# LED_ring.net
KiCad netlist of a schematic drawn in Altium Designer
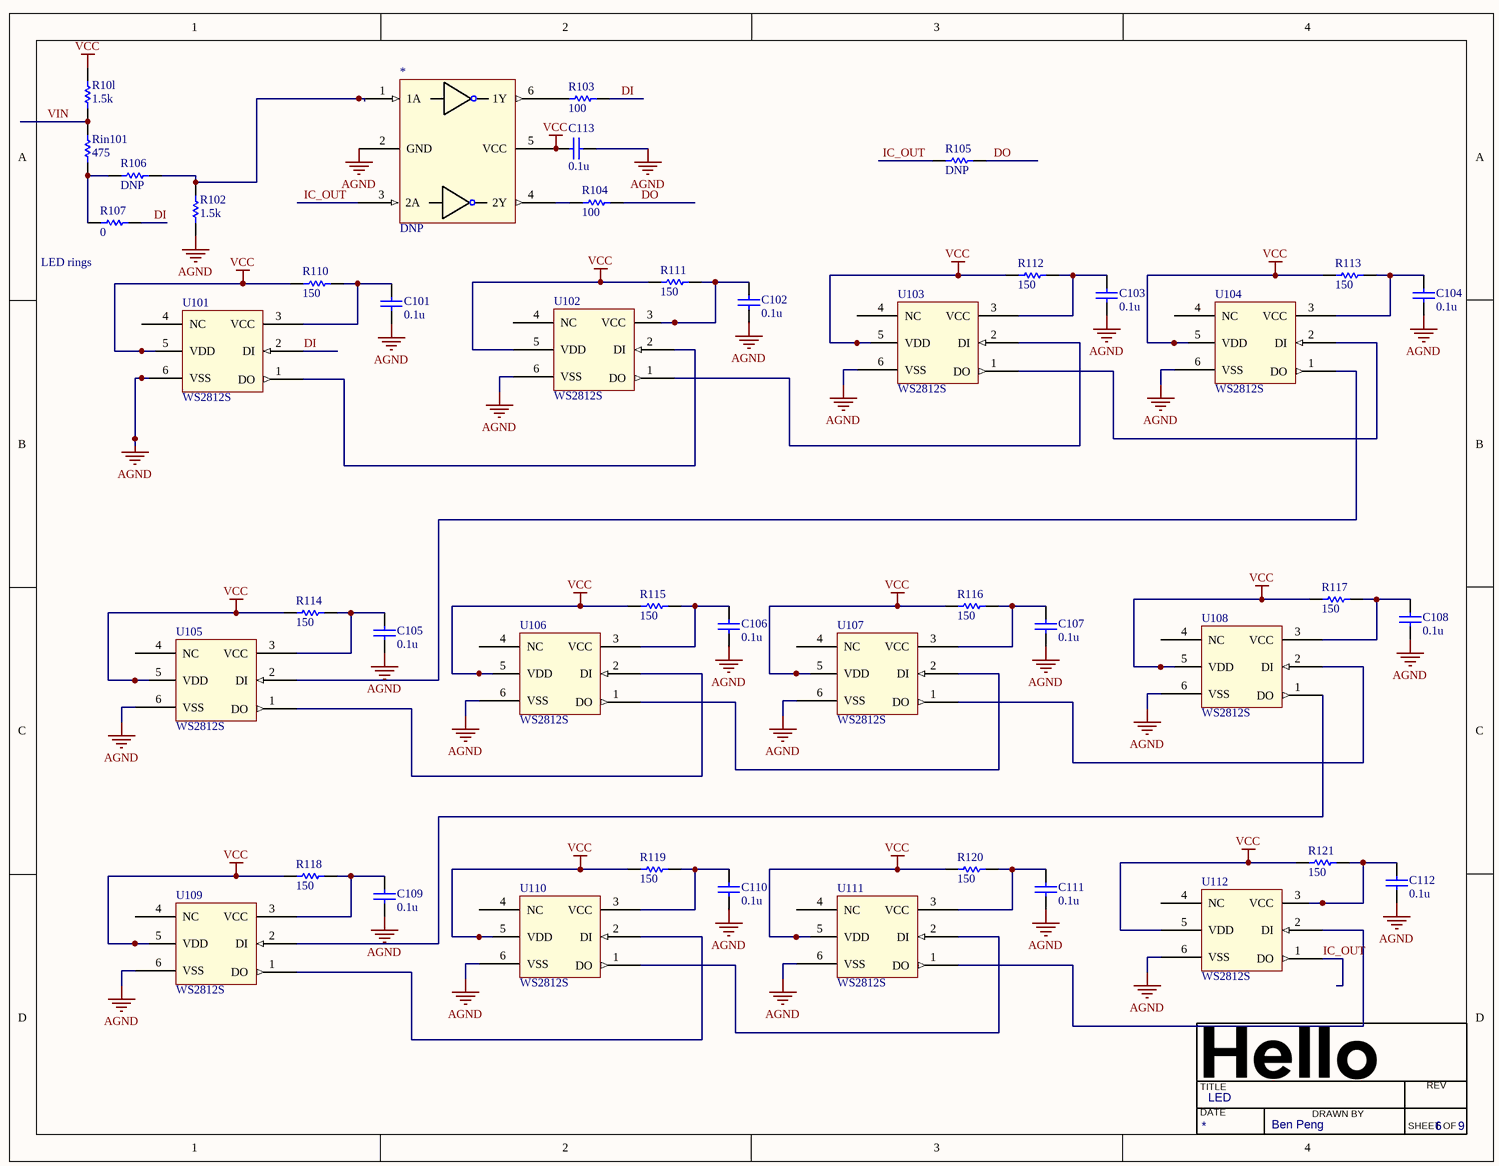
[diagram p0: LED_ring.SchDoc]

(export (version "E")
  (design (tool "Eeschema 10.0.6"))
  (components
    (comp (ref "*")
      (value "DNP")
      (footprint "SOT363-6M")
      (description "Dual inverter The 74HC2G04; 74HCT2G04 is a high-speed Si-gate CMOS device.")
      (libsource (lib "Hello") (part "74HCT2G04"))
    )
    (comp (ref "C101")
      (value "0.1u")
      (footprint "CAP0603_SENSE_DVT")
      (description "Chip capacitor")
      (fields (field (name "TOLERANCE") "10%") (field (name "VOLTAGE") "6.3V"))
      (libsource (lib "Hello") (part "C_10u_10_6.3_X5R_0603"))
    )
    (comp (ref "C102")
      (value "0.1u")
      (footprint "CAP0603_SENSE_DVT")
      (description "Chip capacitor")
      (fields (field (name "TOLERANCE") "10%") (field (name "VOLTAGE") "6.3V"))
      (libsource (lib "Hello") (part "C_10u_10_6.3_X5R_0603"))
    )
    (comp (ref "C103")
      (value "0.1u")
      (footprint "CAP0603_SENSE_DVT")
      (description "Chip capacitor")
      (fields (field (name "TOLERANCE") "10%") (field (name "VOLTAGE") "6.3V"))
      (libsource (lib "Hello") (part "C_10u_10_6.3_X5R_0603"))
    )
    (comp (ref "C104")
      (value "0.1u")
      (footprint "CAP0603_SENSE_DVT")
      (description "Chip capacitor")
      (fields (field (name "TOLERANCE") "10%") (field (name "VOLTAGE") "6.3V"))
      (libsource (lib "Hello") (part "C_10u_10_6.3_X5R_0603"))
    )
    (comp (ref "C105")
      (value "0.1u")
      (footprint "CAP0603_SENSE_DVT")
      (description "Chip capacitor")
      (fields (field (name "TOLERANCE") "10%") (field (name "VOLTAGE") "6.3V"))
      (libsource (lib "Hello") (part "C_10u_10_6.3_X5R_0603"))
    )
    (comp (ref "C106")
      (value "0.1u")
      (footprint "CAP0603_SENSE_DVT")
      (description "Chip capacitor")
      (fields (field (name "TOLERANCE") "10%") (field (name "VOLTAGE") "6.3V"))
      (libsource (lib "Hello") (part "C_10u_10_6.3_X5R_0603"))
    )
    (comp (ref "C107")
      (value "0.1u")
      (footprint "CAP0603_SENSE_DVT")
      (description "Chip capacitor")
      (fields (field (name "TOLERANCE") "10%") (field (name "VOLTAGE") "6.3V"))
      (libsource (lib "Hello") (part "C_10u_10_6.3_X5R_0603"))
    )
    (comp (ref "C108")
      (value "0.1u")
      (footprint "CAP0603_SENSE_DVT")
      (description "Chip capacitor")
      (fields (field (name "TOLERANCE") "10%") (field (name "VOLTAGE") "6.3V"))
      (libsource (lib "Hello") (part "C_10u_10_6.3_X5R_0603"))
    )
    (comp (ref "C109")
      (value "0.1u")
      (footprint "CAP0603_SENSE_DVT")
      (description "Chip capacitor")
      (fields (field (name "TOLERANCE") "10%") (field (name "VOLTAGE") "6.3V"))
      (libsource (lib "Hello") (part "C_10u_10_6.3_X5R_0603"))
    )
    (comp (ref "C110")
      (value "0.1u")
      (footprint "CAP0603_SENSE_DVT")
      (description "Chip capacitor")
      (fields (field (name "TOLERANCE") "10%") (field (name "VOLTAGE") "6.3V"))
      (libsource (lib "Hello") (part "C_10u_10_6.3_X5R_0603"))
    )
    (comp (ref "C111")
      (value "0.1u")
      (footprint "CAP0603_SENSE_DVT")
      (description "Chip capacitor")
      (fields (field (name "TOLERANCE") "10%") (field (name "VOLTAGE") "6.3V"))
      (libsource (lib "Hello") (part "C_10u_10_6.3_X5R_0603"))
    )
    (comp (ref "C112")
      (value "0.1u")
      (footprint "CAP0603_SENSE_DVT")
      (description "Chip capacitor")
      (fields (field (name "TOLERANCE") "10%") (field (name "VOLTAGE") "6.3V"))
      (libsource (lib "Hello") (part "C_10u_10_6.3_X5R_0603"))
    )
    (comp (ref "C113")
      (value "0.1u")
      (footprint "CAP0402_SENSE_DVT")
      (description "Chip capacitor")
      (fields (field (name "TOLERANCE") "10%") (field (name "VOLTAGE") "50V"))
      (libsource (lib "Hello") (part "C_0.1u_10_50_X7R_0402"))
    )
    (comp (ref "R10l")
      (value "1.5k")
      (footprint "RES0402_SENSE_DVT")
      (description "Chip Resistor")
      (fields (field (name "TOLERANCE") "5 %") (field (name "POWER") "0.1 W"))
      (libsource (lib "Hello") (part "R_1.5k_5_0.1_0402"))
    )
    (comp (ref "R102")
      (value "1.5k")
      (footprint "RES0402_SENSE_DVT")
      (description "Chip Resistor")
      (fields (field (name "TOLERANCE") "5 %") (field (name "POWER") "0.1 W"))
      (libsource (lib "Hello") (part "R_1.5k_5_0.1_0402"))
    )
    (comp (ref "R103")
      (value "100")
      (footprint "RES0402_SENSE_DVT")
      (description "Chip Resistor")
      (fields (field (name "TOLERANCE") "1 %") (field (name "POWER") "0.1 W"))
      (libsource (lib "Hello") (part "R_100_1_0.1_0402"))
    )
    (comp (ref "R104")
      (value "100")
      (footprint "RES0402_SENSE_DVT")
      (description "Chip Resistor")
      (fields (field (name "TOLERANCE") "1 %") (field (name "POWER") "0.1 W"))
      (libsource (lib "Hello") (part "R_100_1_0.1_0402"))
    )
    (comp (ref "R105")
      (value "DNP")
      (footprint "RES0402_SENSE_DVT")
      (description "Chip Resistor")
      (fields (field (name "TOLERANCE") "1 %") (field (name "POWER") "0.1 W"))
      (libsource (lib "Hello") (part "R_100_1_0.1_0402"))
    )
    (comp (ref "R106")
      (value "DNP")
      (footprint "RES0402_SENSE_DVT")
      (description "Chip Resistor")
      (fields (field (name "TOLERANCE") "Jumper") (field (name "POWER") "0.1 W"))
      (libsource (lib "Hello") (part "R_0_jumper_0.1_0402"))
    )
    (comp (ref "R107")
      (value "0")
      (footprint "RES0402_SENSE_DVT")
      (description "Chip Resistor")
      (fields (field (name "TOLERANCE") "Jumper") (field (name "POWER") "0.1 W"))
      (libsource (lib "Hello") (part "R_0_jumper_0.1_0402"))
    )
    (comp (ref "R110")
      (value "150")
      (footprint "RES0402_SENSE_DVT")
      (description "Chip Resistor")
      (fields (field (name "TOLERANCE") "1 %") (field (name "POWER") "0.1 W"))
      (libsource (lib "Hello") (part "R_150_1_0.1_0402"))
    )
    (comp (ref "R111")
      (value "150")
      (footprint "RES0402_SENSE_DVT")
      (description "Chip Resistor")
      (fields (field (name "TOLERANCE") "1 %") (field (name "POWER") "0.1 W"))
      (libsource (lib "Hello") (part "R_150_1_0.1_0402"))
    )
    (comp (ref "R112")
      (value "150")
      (footprint "RES0402_SENSE_DVT")
      (description "Chip Resistor")
      (fields (field (name "TOLERANCE") "1 %") (field (name "POWER") "0.1 W"))
      (libsource (lib "Hello") (part "R_150_1_0.1_0402"))
    )
    (comp (ref "R113")
      (value "150")
      (footprint "RES0402_SENSE_DVT")
      (description "Chip Resistor")
      (fields (field (name "TOLERANCE") "1 %") (field (name "POWER") "0.1 W"))
      (libsource (lib "Hello") (part "R_150_1_0.1_0402"))
    )
    (comp (ref "R114")
      (value "150")
      (footprint "RES0402_SENSE_DVT")
      (description "Chip Resistor")
      (fields (field (name "TOLERANCE") "1 %") (field (name "POWER") "0.1 W"))
      (libsource (lib "Hello") (part "R_150_1_0.1_0402"))
    )
    (comp (ref "R115")
      (value "150")
      (footprint "RES0402_SENSE_DVT")
      (description "Chip Resistor")
      (fields (field (name "TOLERANCE") "1 %") (field (name "POWER") "0.1 W"))
      (libsource (lib "Hello") (part "R_150_1_0.1_0402"))
    )
    (comp (ref "R116")
      (value "150")
      (footprint "RES0402_SENSE_DVT")
      (description "Chip Resistor")
      (fields (field (name "TOLERANCE") "1 %") (field (name "POWER") "0.1 W"))
      (libsource (lib "Hello") (part "R_150_1_0.1_0402"))
    )
    (comp (ref "R117")
      (value "150")
      (footprint "RES0402_SENSE_DVT")
      (description "Chip Resistor")
      (fields (field (name "TOLERANCE") "1 %") (field (name "POWER") "0.1 W"))
      (libsource (lib "Hello") (part "R_150_1_0.1_0402"))
    )
    (comp (ref "R118")
      (value "150")
      (footprint "RES0402_SENSE_DVT")
      (description "Chip Resistor")
      (fields (field (name "TOLERANCE") "1 %") (field (name "POWER") "0.1 W"))
      (libsource (lib "Hello") (part "R_150_1_0.1_0402"))
    )
    (comp (ref "R119")
      (value "150")
      (footprint "RES0402_SENSE_DVT")
      (description "Chip Resistor")
      (fields (field (name "TOLERANCE") "1 %") (field (name "POWER") "0.1 W"))
      (libsource (lib "Hello") (part "R_150_1_0.1_0402"))
    )
    (comp (ref "R120")
      (value "150")
      (footprint "RES0402_SENSE_DVT")
      (description "Chip Resistor")
      (fields (field (name "TOLERANCE") "1 %") (field (name "POWER") "0.1 W"))
      (libsource (lib "Hello") (part "R_150_1_0.1_0402"))
    )
    (comp (ref "R121")
      (value "150")
      (footprint "RES0402_SENSE_DVT")
      (description "Chip Resistor")
      (fields (field (name "TOLERANCE") "1 %") (field (name "POWER") "0.1 W"))
      (libsource (lib "Hello") (part "R_150_1_0.1_0402"))
    )
    (comp (ref "Rin101")
      (value "475")
      (footprint "RES0402_SENSE_DVT")
      (description "Chip Resistor")
      (fields (field (name "TOLERANCE") "1 %") (field (name "POWER") "0.1 W"))
      (libsource (lib "Hello") (part "R_475_1_0.1_0402"))
    )
    (comp (ref "U101")
      (value "WS2812S")
      (footprint "6PIN_WS2812")
      (description "WS2812 Intelligent control LED integrated light source")
      (libsource (lib "Hello") (part "WS2812"))
    )
    (comp (ref "U102")
      (value "WS2812S")
      (footprint "6PIN_WS2812")
      (description "WS2812 Intelligent control LED integrated light source")
      (libsource (lib "Hello") (part "WS2812"))
    )
    (comp (ref "U103")
      (value "WS2812S")
      (footprint "6PIN_WS2812")
      (description "WS2812 Intelligent control LED integrated light source")
      (libsource (lib "Hello") (part "WS2812"))
    )
    (comp (ref "U104")
      (value "WS2812S")
      (footprint "6PIN_WS2812")
      (description "WS2812 Intelligent control LED integrated light source")
      (libsource (lib "Hello") (part "WS2812"))
    )
    (comp (ref "U105")
      (value "WS2812S")
      (footprint "6PIN_WS2812")
      (description "WS2812 Intelligent control LED integrated light source")
      (libsource (lib "Hello") (part "WS2812"))
    )
    (comp (ref "U106")
      (value "WS2812S")
      (footprint "6PIN_WS2812")
      (description "WS2812 Intelligent control LED integrated light source")
      (libsource (lib "Hello") (part "WS2812"))
    )
    (comp (ref "U107")
      (value "WS2812S")
      (footprint "6PIN_WS2812")
      (description "WS2812 Intelligent control LED integrated light source")
      (libsource (lib "Hello") (part "WS2812"))
    )
    (comp (ref "U108")
      (value "WS2812S")
      (footprint "6PIN_WS2812")
      (description "WS2812 Intelligent control LED integrated light source")
      (libsource (lib "Hello") (part "WS2812"))
    )
    (comp (ref "U109")
      (value "WS2812S")
      (footprint "6PIN_WS2812")
      (description "WS2812 Intelligent control LED integrated light source")
      (libsource (lib "Hello") (part "WS2812"))
    )
    (comp (ref "U110")
      (value "WS2812S")
      (footprint "6PIN_WS2812")
      (description "WS2812 Intelligent control LED integrated light source")
      (libsource (lib "Hello") (part "WS2812"))
    )
    (comp (ref "U111")
      (value "WS2812S")
      (footprint "6PIN_WS2812")
      (description "WS2812 Intelligent control LED integrated light source")
      (libsource (lib "Hello") (part "WS2812"))
    )
    (comp (ref "U112")
      (value "WS2812S")
      (footprint "6PIN_WS2812")
      (description "WS2812 Intelligent control LED integrated light source")
      (libsource (lib "Hello") (part "WS2812"))
    )
  )
  (nets
    (net (code "1") (name "/DI") (class "Default")
      (node (ref "R103") (pin "2") (pinfunction "2_2") (pintype "passive"))
      (node (ref "R107") (pin "2") (pinfunction "2_2") (pintype "passive"))
      (node (ref "U101") (pin "2") (pinfunction "DI_2") (pintype "input"))
    )
    (net (code "2") (name "/DO") (class "Default")
      (node (ref "R104") (pin "2") (pinfunction "2_2") (pintype "passive"))
      (node (ref "R105") (pin "2") (pinfunction "2_2") (pintype "passive"))
    )
    (net (code "3") (name "/IC_OUT") (class "Default")
      (node (ref "*") (pin "3") (pinfunction "2A_3") (pintype "input"))
      (node (ref "R105") (pin "1") (pinfunction "1_1") (pintype "passive"))
      (node (ref "U112") (pin "1") (pinfunction "DO_1") (pintype "output"))
    )
    (net (code "4") (name "/VIN") (class "Default")
      (node (ref "R10l") (pin "1") (pinfunction "1_1") (pintype "passive"))
      (node (ref "Rin101") (pin "2") (pinfunction "2_2") (pintype "passive"))
    )
    (net (code "5") (name "AGND") (class "Default")
      (node (ref "*") (pin "2") (pinfunction "GND_2") (pintype "power_in"))
      (node (ref "C101") (pin "1") (pinfunction "1_1") (pintype "passive"))
      (node (ref "C102") (pin "1") (pinfunction "1_1") (pintype "passive"))
      (node (ref "C103") (pin "1") (pinfunction "1_1") (pintype "passive"))
      (node (ref "C104") (pin "1") (pinfunction "1_1") (pintype "passive"))
      (node (ref "C105") (pin "1") (pinfunction "1_1") (pintype "passive"))
      (node (ref "C106") (pin "1") (pinfunction "1_1") (pintype "passive"))
      (node (ref "C107") (pin "1") (pinfunction "1_1") (pintype "passive"))
      (node (ref "C108") (pin "1") (pinfunction "1_1") (pintype "passive"))
      (node (ref "C109") (pin "1") (pinfunction "1_1") (pintype "passive"))
      (node (ref "C110") (pin "1") (pinfunction "1_1") (pintype "passive"))
      (node (ref "C111") (pin "1") (pinfunction "1_1") (pintype "passive"))
      (node (ref "C112") (pin "1") (pinfunction "1_1") (pintype "passive"))
      (node (ref "C113") (pin "2") (pinfunction "2_2") (pintype "passive"))
      (node (ref "R102") (pin "1") (pinfunction "1_1") (pintype "passive"))
      (node (ref "U101") (pin "6") (pinfunction "VSS_6") (pintype "power_in"))
      (node (ref "U102") (pin "6") (pinfunction "VSS_6") (pintype "power_in"))
      (node (ref "U103") (pin "6") (pinfunction "VSS_6") (pintype "power_in"))
      (node (ref "U104") (pin "6") (pinfunction "VSS_6") (pintype "power_in"))
      (node (ref "U105") (pin "6") (pinfunction "VSS_6") (pintype "power_in"))
      (node (ref "U106") (pin "6") (pinfunction "VSS_6") (pintype "power_in"))
      (node (ref "U107") (pin "6") (pinfunction "VSS_6") (pintype "power_in"))
      (node (ref "U108") (pin "6") (pinfunction "VSS_6") (pintype "power_in"))
      (node (ref "U109") (pin "6") (pinfunction "VSS_6") (pintype "power_in"))
      (node (ref "U110") (pin "6") (pinfunction "VSS_6") (pintype "power_in"))
      (node (ref "U111") (pin "6") (pinfunction "VSS_6") (pintype "power_in"))
      (node (ref "U112") (pin "6") (pinfunction "VSS_6") (pintype "power_in"))
    )
    (net (code "6") (name "Net-(*-1A)") (class "Default")
      (node (ref "*") (pin "1") (pinfunction "1A_1") (pintype "input"))
      (node (ref "R102") (pin "2") (pinfunction "2_2") (pintype "passive"))
      (node (ref "R106") (pin "2") (pinfunction "2_2") (pintype "passive"))
    )
    (net (code "7") (name "Net-(*-1Y)") (class "Default")
      (node (ref "*") (pin "6") (pinfunction "1Y_6") (pintype "output"))
      (node (ref "R103") (pin "1") (pinfunction "1_1") (pintype "passive"))
    )
    (net (code "8") (name "Net-(*-2Y)") (class "Default")
      (node (ref "*") (pin "4") (pinfunction "2Y_4") (pintype "output"))
      (node (ref "R104") (pin "1") (pinfunction "1_1") (pintype "passive"))
    )
    (net (code "9") (name "Net-(R106-Pad1)") (class "Default")
      (node (ref "R106") (pin "1") (pinfunction "1_1") (pintype "passive"))
      (node (ref "R107") (pin "1") (pinfunction "1_1") (pintype "passive"))
      (node (ref "Rin101") (pin "1") (pinfunction "1_1") (pintype "passive"))
    )
    (net (code "10") (name "Net-(U101-DO)") (class "Default")
      (node (ref "U101") (pin "1") (pinfunction "DO_1") (pintype "output"))
      (node (ref "U102") (pin "2") (pinfunction "DI_2") (pintype "input"))
    )
    (net (code "11") (name "Net-(U101-VCC)") (class "Default")
      (node (ref "C101") (pin "2") (pinfunction "2_2") (pintype "passive"))
      (node (ref "R110") (pin "1") (pinfunction "1_1") (pintype "passive"))
      (node (ref "U101") (pin "3") (pinfunction "VCC_3") (pintype "power_in"))
    )
    (net (code "12") (name "Net-(U102-DO)") (class "Default")
      (node (ref "U102") (pin "1") (pinfunction "DO_1") (pintype "output"))
      (node (ref "U103") (pin "2") (pinfunction "DI_2") (pintype "input"))
    )
    (net (code "13") (name "Net-(U102-VCC)") (class "Default")
      (node (ref "C102") (pin "2") (pinfunction "2_2") (pintype "passive"))
      (node (ref "R111") (pin "1") (pinfunction "1_1") (pintype "passive"))
      (node (ref "U102") (pin "3") (pinfunction "VCC_3") (pintype "power_in"))
    )
    (net (code "14") (name "Net-(U103-DO)") (class "Default")
      (node (ref "U103") (pin "1") (pinfunction "DO_1") (pintype "output"))
      (node (ref "U104") (pin "2") (pinfunction "DI_2") (pintype "input"))
    )
    (net (code "15") (name "Net-(U103-VCC)") (class "Default")
      (node (ref "C103") (pin "2") (pinfunction "2_2") (pintype "passive"))
      (node (ref "R112") (pin "1") (pinfunction "1_1") (pintype "passive"))
      (node (ref "U103") (pin "3") (pinfunction "VCC_3") (pintype "power_in"))
    )
    (net (code "16") (name "Net-(U104-DO)") (class "Default")
      (node (ref "U104") (pin "1") (pinfunction "DO_1") (pintype "output"))
      (node (ref "U105") (pin "2") (pinfunction "DI_2") (pintype "input"))
    )
    (net (code "17") (name "Net-(U104-VCC)") (class "Default")
      (node (ref "C104") (pin "2") (pinfunction "2_2") (pintype "passive"))
      (node (ref "R113") (pin "1") (pinfunction "1_1") (pintype "passive"))
      (node (ref "U104") (pin "3") (pinfunction "VCC_3") (pintype "power_in"))
    )
    (net (code "18") (name "Net-(U105-DO)") (class "Default")
      (node (ref "U105") (pin "1") (pinfunction "DO_1") (pintype "output"))
      (node (ref "U106") (pin "2") (pinfunction "DI_2") (pintype "input"))
    )
    (net (code "19") (name "Net-(U105-VCC)") (class "Default")
      (node (ref "C105") (pin "2") (pinfunction "2_2") (pintype "passive"))
      (node (ref "R114") (pin "1") (pinfunction "1_1") (pintype "passive"))
      (node (ref "U105") (pin "3") (pinfunction "VCC_3") (pintype "power_in"))
    )
    (net (code "20") (name "Net-(U106-DO)") (class "Default")
      (node (ref "U106") (pin "1") (pinfunction "DO_1") (pintype "output"))
      (node (ref "U107") (pin "2") (pinfunction "DI_2") (pintype "input"))
    )
    (net (code "21") (name "Net-(U106-VCC)") (class "Default")
      (node (ref "C106") (pin "2") (pinfunction "2_2") (pintype "passive"))
      (node (ref "R115") (pin "1") (pinfunction "1_1") (pintype "passive"))
      (node (ref "U106") (pin "3") (pinfunction "VCC_3") (pintype "power_in"))
    )
    (net (code "22") (name "Net-(U107-DO)") (class "Default")
      (node (ref "U107") (pin "1") (pinfunction "DO_1") (pintype "output"))
      (node (ref "U108") (pin "2") (pinfunction "DI_2") (pintype "input"))
    )
    (net (code "23") (name "Net-(U107-VCC)") (class "Default")
      (node (ref "C107") (pin "2") (pinfunction "2_2") (pintype "passive"))
      (node (ref "R116") (pin "1") (pinfunction "1_1") (pintype "passive"))
      (node (ref "U107") (pin "3") (pinfunction "VCC_3") (pintype "power_in"))
    )
    (net (code "24") (name "Net-(U108-DO)") (class "Default")
      (node (ref "U108") (pin "1") (pinfunction "DO_1") (pintype "output"))
      (node (ref "U109") (pin "2") (pinfunction "DI_2") (pintype "input"))
    )
    (net (code "25") (name "Net-(U108-VCC)") (class "Default")
      (node (ref "C108") (pin "2") (pinfunction "2_2") (pintype "passive"))
      (node (ref "R117") (pin "1") (pinfunction "1_1") (pintype "passive"))
      (node (ref "U108") (pin "3") (pinfunction "VCC_3") (pintype "power_in"))
    )
    (net (code "26") (name "Net-(U109-DO)") (class "Default")
      (node (ref "U109") (pin "1") (pinfunction "DO_1") (pintype "output"))
      (node (ref "U110") (pin "2") (pinfunction "DI_2") (pintype "input"))
    )
    (net (code "27") (name "Net-(U109-VCC)") (class "Default")
      (node (ref "C109") (pin "2") (pinfunction "2_2") (pintype "passive"))
      (node (ref "R118") (pin "1") (pinfunction "1_1") (pintype "passive"))
      (node (ref "U109") (pin "3") (pinfunction "VCC_3") (pintype "power_in"))
    )
    (net (code "28") (name "Net-(U110-DO)") (class "Default")
      (node (ref "U110") (pin "1") (pinfunction "DO_1") (pintype "output"))
      (node (ref "U111") (pin "2") (pinfunction "DI_2") (pintype "input"))
    )
    (net (code "29") (name "Net-(U110-VCC)") (class "Default")
      (node (ref "C110") (pin "2") (pinfunction "2_2") (pintype "passive"))
      (node (ref "R119") (pin "1") (pinfunction "1_1") (pintype "passive"))
      (node (ref "U110") (pin "3") (pinfunction "VCC_3") (pintype "power_in"))
    )
    (net (code "30") (name "Net-(U111-DO)") (class "Default")
      (node (ref "U111") (pin "1") (pinfunction "DO_1") (pintype "output"))
      (node (ref "U112") (pin "2") (pinfunction "DI_2") (pintype "input"))
    )
    (net (code "31") (name "Net-(U111-VCC)") (class "Default")
      (node (ref "C111") (pin "2") (pinfunction "2_2") (pintype "passive"))
      (node (ref "R120") (pin "1") (pinfunction "1_1") (pintype "passive"))
      (node (ref "U111") (pin "3") (pinfunction "VCC_3") (pintype "power_in"))
    )
    (net (code "32") (name "Net-(U112-VCC)") (class "Default")
      (node (ref "C112") (pin "2") (pinfunction "2_2") (pintype "passive"))
      (node (ref "R121") (pin "1") (pinfunction "1_1") (pintype "passive"))
      (node (ref "U112") (pin "3") (pinfunction "VCC_3") (pintype "power_in"))
    )
    (net (code "33") (name "VCC") (class "Default")
      (node (ref "*") (pin "5") (pinfunction "VCC_5") (pintype "power_in"))
      (node (ref "C113") (pin "1") (pinfunction "1_1") (pintype "passive"))
      (node (ref "R10l") (pin "2") (pinfunction "2_2") (pintype "passive"))
      (node (ref "R110") (pin "2") (pinfunction "2_2") (pintype "passive"))
      (node (ref "R111") (pin "2") (pinfunction "2_2") (pintype "passive"))
      (node (ref "R112") (pin "2") (pinfunction "2_2") (pintype "passive"))
      (node (ref "R113") (pin "2") (pinfunction "2_2") (pintype "passive"))
      (node (ref "R114") (pin "2") (pinfunction "2_2") (pintype "passive"))
      (node (ref "R115") (pin "2") (pinfunction "2_2") (pintype "passive"))
      (node (ref "R116") (pin "2") (pinfunction "2_2") (pintype "passive"))
      (node (ref "R117") (pin "2") (pinfunction "2_2") (pintype "passive"))
      (node (ref "R118") (pin "2") (pinfunction "2_2") (pintype "passive"))
      (node (ref "R119") (pin "2") (pinfunction "2_2") (pintype "passive"))
      (node (ref "R120") (pin "2") (pinfunction "2_2") (pintype "passive"))
      (node (ref "R121") (pin "2") (pinfunction "2_2") (pintype "passive"))
      (node (ref "U101") (pin "5") (pinfunction "VDD_5") (pintype "power_in"))
      (node (ref "U102") (pin "5") (pinfunction "VDD_5") (pintype "power_in"))
      (node (ref "U103") (pin "5") (pinfunction "VDD_5") (pintype "power_in"))
      (node (ref "U104") (pin "5") (pinfunction "VDD_5") (pintype "power_in"))
      (node (ref "U105") (pin "5") (pinfunction "VDD_5") (pintype "power_in"))
      (node (ref "U106") (pin "5") (pinfunction "VDD_5") (pintype "power_in"))
      (node (ref "U107") (pin "5") (pinfunction "VDD_5") (pintype "power_in"))
      (node (ref "U108") (pin "5") (pinfunction "VDD_5") (pintype "power_in"))
      (node (ref "U109") (pin "5") (pinfunction "VDD_5") (pintype "power_in"))
      (node (ref "U110") (pin "5") (pinfunction "VDD_5") (pintype "power_in"))
      (node (ref "U111") (pin "5") (pinfunction "VDD_5") (pintype "power_in"))
      (node (ref "U112") (pin "5") (pinfunction "VDD_5") (pintype "power_in"))
    )
    (net (code "34") (name "unconnected-(U101-NC-Pad4)") (class "Default")
      (node (ref "U101") (pin "4") (pinfunction "NC_4") (pintype "passive"))
    )
    (net (code "35") (name "unconnected-(U102-NC-Pad4)") (class "Default")
      (node (ref "U102") (pin "4") (pinfunction "NC_4") (pintype "passive"))
    )
    (net (code "36") (name "unconnected-(U103-NC-Pad4)") (class "Default")
      (node (ref "U103") (pin "4") (pinfunction "NC_4") (pintype "passive"))
    )
    (net (code "37") (name "unconnected-(U104-NC-Pad4)") (class "Default")
      (node (ref "U104") (pin "4") (pinfunction "NC_4") (pintype "passive"))
    )
    (net (code "38") (name "unconnected-(U105-NC-Pad4)") (class "Default")
      (node (ref "U105") (pin "4") (pinfunction "NC_4") (pintype "passive"))
    )
    (net (code "39") (name "unconnected-(U106-NC-Pad4)") (class "Default")
      (node (ref "U106") (pin "4") (pinfunction "NC_4") (pintype "passive"))
    )
    (net (code "40") (name "unconnected-(U107-NC-Pad4)") (class "Default")
      (node (ref "U107") (pin "4") (pinfunction "NC_4") (pintype "passive"))
    )
    (net (code "41") (name "unconnected-(U108-NC-Pad4)") (class "Default")
      (node (ref "U108") (pin "4") (pinfunction "NC_4") (pintype "passive"))
    )
    (net (code "42") (name "unconnected-(U109-NC-Pad4)") (class "Default")
      (node (ref "U109") (pin "4") (pinfunction "NC_4") (pintype "passive"))
    )
    (net (code "43") (name "unconnected-(U110-NC-Pad4)") (class "Default")
      (node (ref "U110") (pin "4") (pinfunction "NC_4") (pintype "passive"))
    )
    (net (code "44") (name "unconnected-(U111-NC-Pad4)") (class "Default")
      (node (ref "U111") (pin "4") (pinfunction "NC_4") (pintype "passive"))
    )
    (net (code "45") (name "unconnected-(U112-NC-Pad4)") (class "Default")
      (node (ref "U112") (pin "4") (pinfunction "NC_4") (pintype "passive"))
    )
  )
)
